# I2C_Sheet.net
KiCad netlist of a schematic drawn in Altium Designer
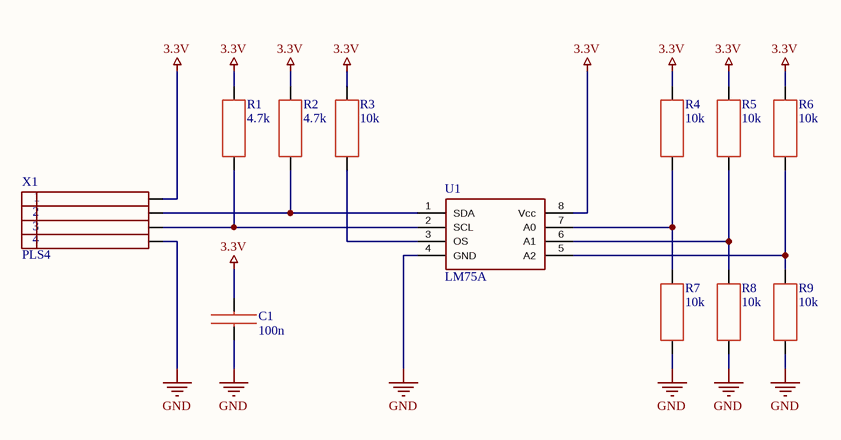
[diagram p0: I2C_Sheet.SchDoc]

(export (version "E")
  (design (tool "Eeschema 10.0.6"))
  (components
    (comp (ref "C1")
      (value "100n")
      (footprint "Capacitor:CC0805_3D")
      (libsource (lib "Capacitor") (part "CC0805 X uF"))
    )
    (comp (ref "R1")
      (value "4.7k")
      (footprint "Resistor:RC0805_3D")
      (libsource (lib "Resistor") (part "RC0805 X Ohm"))
    )
    (comp (ref "R2")
      (value "4.7k")
      (footprint "Resistor:RC0805_3D")
      (libsource (lib "Resistor") (part "RC0805 X Ohm"))
    )
    (comp (ref "R3")
      (value "10k")
      (footprint "Resistor:RC0805_3D")
      (libsource (lib "Resistor") (part "RC0805 X Ohm"))
    )
    (comp (ref "R4")
      (value "10k")
      (footprint "Resistor:RC0805_3D")
      (libsource (lib "Resistor") (part "RC0805 X Ohm"))
    )
    (comp (ref "R5")
      (value "10k")
      (footprint "Resistor:RC0805_3D")
      (libsource (lib "Resistor") (part "RC0805 X Ohm"))
    )
    (comp (ref "R6")
      (value "10k")
      (footprint "Resistor:RC0805_3D")
      (libsource (lib "Resistor") (part "RC0805 X Ohm"))
    )
    (comp (ref "R7")
      (value "10k")
      (footprint "Resistor:RC0805_3D")
      (libsource (lib "Resistor") (part "RC0805 X Ohm"))
    )
    (comp (ref "R8")
      (value "10k")
      (footprint "Resistor:RC0805_3D")
      (libsource (lib "Resistor") (part "RC0805 X Ohm"))
    )
    (comp (ref "R9")
      (value "10k")
      (footprint "Resistor:RC0805_3D")
      (libsource (lib "Resistor") (part "RC0805 X Ohm"))
    )
    (comp (ref "U1") (value "LM75A") (footprint "SOIC-8") (libsource (lib "LM75A") (part "LM75A")))
    (comp (ref "X1")
      (value "PLS4")
      (footprint "PLS_Connector:PLS4")
      (libsource (lib "PLS_Connector") (part "PLS4"))
    )
  )
  (nets
    (net (code "1") (name "3.3V") (class "Default")
      (node (ref "C1") (pin "2") (pinfunction "2_2") (pintype "passive"))
      (node (ref "R1") (pin "2") (pinfunction "2_2") (pintype "passive"))
      (node (ref "R2") (pin "2") (pinfunction "2_2") (pintype "passive"))
      (node (ref "R3") (pin "2") (pinfunction "2_2") (pintype "passive"))
      (node (ref "R4") (pin "2") (pinfunction "2_2") (pintype "passive"))
      (node (ref "R5") (pin "2") (pinfunction "2_2") (pintype "passive"))
      (node (ref "R6") (pin "2") (pinfunction "2_2") (pintype "passive"))
      (node (ref "U1") (pin "8") (pinfunction "Vcc_8") (pintype "passive"))
      (node (ref "X1") (pin "1") (pintype "passive"))
    )
    (net (code "2") (name "GND") (class "Default")
      (node (ref "C1") (pin "1") (pinfunction "1_1") (pintype "passive"))
      (node (ref "R7") (pin "1") (pinfunction "1_1") (pintype "passive"))
      (node (ref "R8") (pin "1") (pinfunction "1_1") (pintype "passive"))
      (node (ref "R9") (pin "1") (pinfunction "1_1") (pintype "passive"))
      (node (ref "U1") (pin "4") (pinfunction "GND_4") (pintype "passive"))
      (node (ref "X1") (pin "4") (pintype "passive"))
    )
    (net (code "3") (name "Net-(U1-A0)") (class "Default")
      (node (ref "R4") (pin "1") (pinfunction "1_1") (pintype "passive"))
      (node (ref "R7") (pin "2") (pinfunction "2_2") (pintype "passive"))
      (node (ref "U1") (pin "7") (pinfunction "A0_7") (pintype "passive"))
    )
    (net (code "4") (name "Net-(U1-A1)") (class "Default")
      (node (ref "R5") (pin "1") (pinfunction "1_1") (pintype "passive"))
      (node (ref "R8") (pin "2") (pinfunction "2_2") (pintype "passive"))
      (node (ref "U1") (pin "6") (pinfunction "A1_6") (pintype "passive"))
    )
    (net (code "5") (name "Net-(U1-A2)") (class "Default")
      (node (ref "R6") (pin "1") (pinfunction "1_1") (pintype "passive"))
      (node (ref "R9") (pin "2") (pinfunction "2_2") (pintype "passive"))
      (node (ref "U1") (pin "5") (pinfunction "A2_5") (pintype "passive"))
    )
    (net (code "6") (name "Net-(U1-OS)") (class "Default")
      (node (ref "R3") (pin "1") (pinfunction "1_1") (pintype "passive"))
      (node (ref "U1") (pin "3") (pinfunction "OS_3") (pintype "passive"))
    )
    (net (code "7") (name "Net-(U1-SCL)") (class "Default")
      (node (ref "R1") (pin "1") (pinfunction "1_1") (pintype "passive"))
      (node (ref "U1") (pin "2") (pinfunction "SCL_2") (pintype "passive"))
      (node (ref "X1") (pin "3") (pintype "passive"))
    )
    (net (code "8") (name "Net-(U1-SDA)") (class "Default")
      (node (ref "R2") (pin "1") (pinfunction "1_1") (pintype "passive"))
      (node (ref "U1") (pin "1") (pinfunction "SDA_1") (pintype "passive"))
      (node (ref "X1") (pin "2") (pintype "passive"))
    )
  )
)
